# clock_generator.net
KiCad netlist of a schematic drawn in Altium Designer
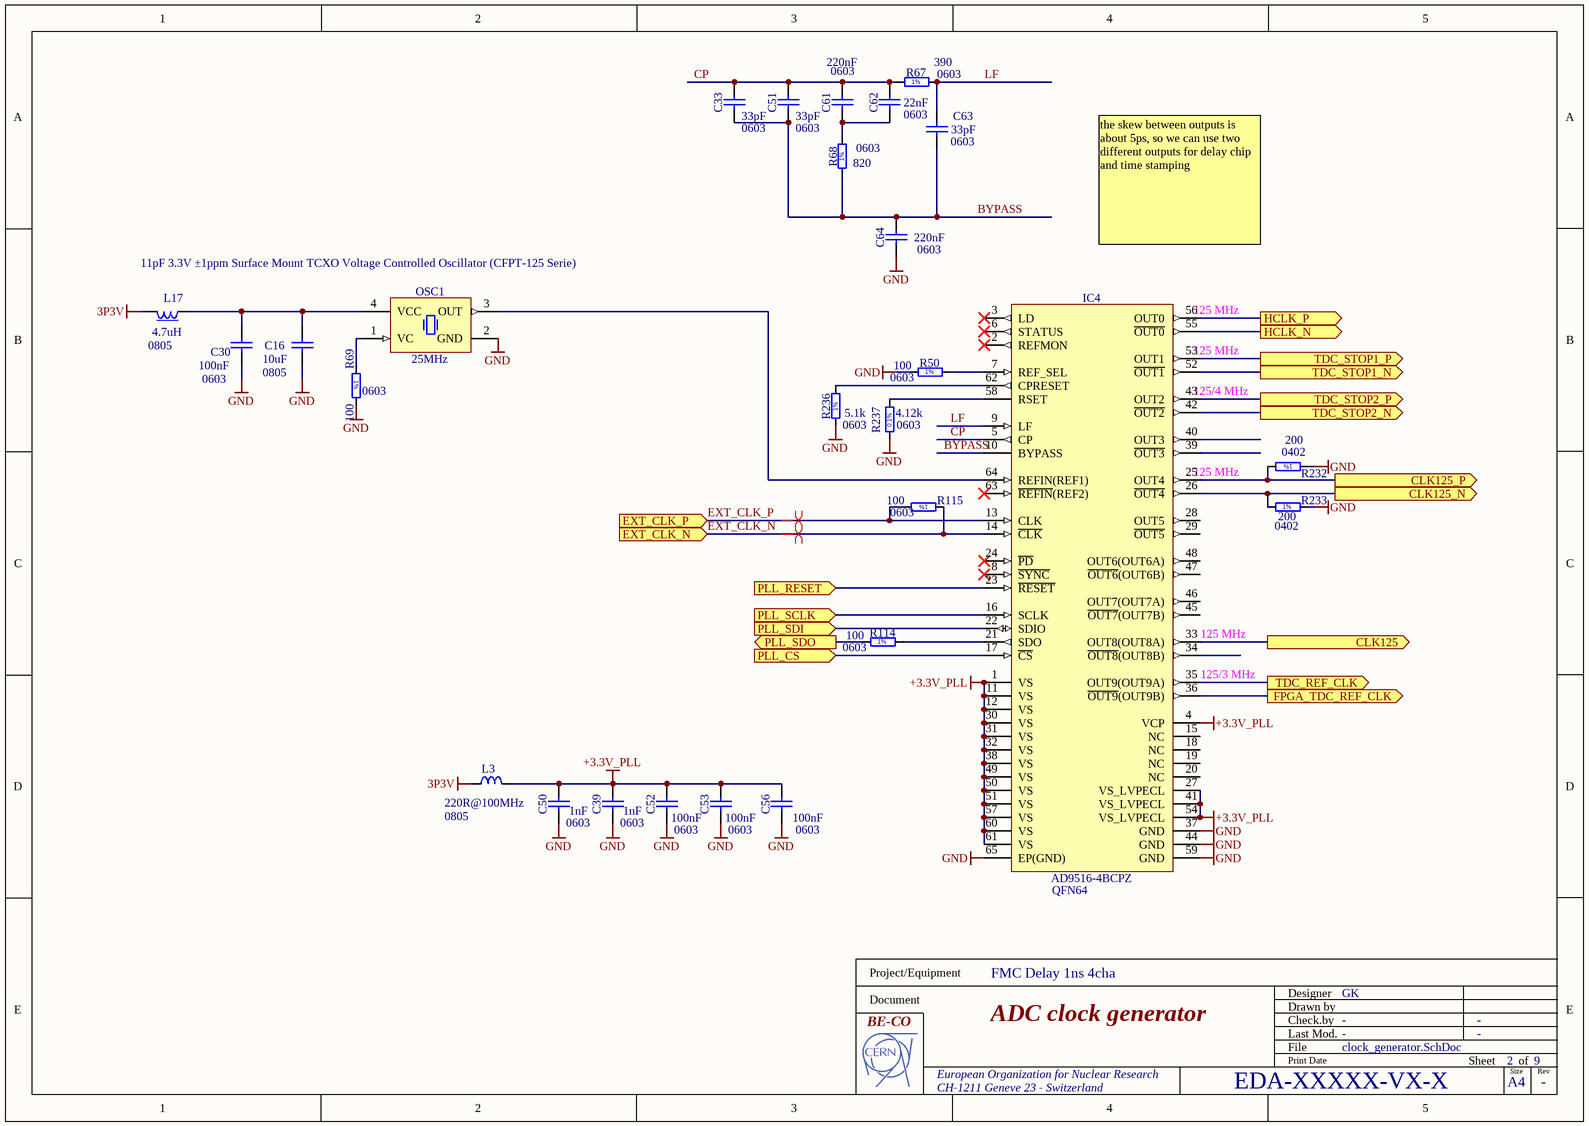
[diagram p0: clock_generator.SchDoc]

(export (version "E")
  (design (tool "Eeschema 10.0.6"))
  (components
    (comp (ref "C16")
      (value "10uF")
      (footprint "CAPC2012X135N")
      (description "Non-polarised capacitor")
      (fields
        (field (name "PART NUMBER") "CC0805_10UF_16V_10%_X5R")
        (field (name "VOLTAGE") "16V")
        (field (name "CASE") "0805")
        (field (name "AUTHOR") "CERN DEM JLC")
      )
      (libsource (lib "Capacitors") (part "Capacitor - non polarized"))
    )
    (comp (ref "C30")
      (value "100nF")
      (footprint "CAPC1608X87N")
      (description "Non-polarised capacitor")
      (fields
        (field (name "CASE") "0603")
        (field (name "MANUFACTURER1 PART NUMBER") "223858615649")
        (field (name "MANUFACTURER") "GENERIC")
        (field (name "AUTHOR") "CERN DEM JLC")
      )
      (libsource (lib "Capacitors") (part "Capacitor - non polarized"))
    )
    (comp (ref "C33")
      (value "33pF")
      (footprint "CAPC1608X87N")
      (description "Non-polarised capacitor")
      (fields
        (field (name "PART NUMBER") "CC0603_33PF_50V_5%_NP0")
        (field (name "VOLTAGE") "50V")
        (field (name "CASE") "0603")
        (field (name "AUTHOR") "CERN DEM JLC")
      )
      (libsource (lib "Capacitors") (part "Capacitor - non polarized"))
    )
    (comp (ref "C39")
      (value "1nF")
      (footprint "CAPC1608X87N")
      (description "Non-polarised capacitor")
      (fields
        (field (name "PART NUMBER") "CC0603_1NF_50V_10%_X7R")
        (field (name "VOLTAGE") "50V")
        (field (name "CASE") "0603")
        (field (name "AUTHOR") "CERN DEM JLC")
      )
      (libsource (lib "Capacitors") (part "Capacitor - non polarized"))
    )
    (comp (ref "C50")
      (value "1nF")
      (footprint "CAPC1608X87N")
      (description "Non-polarised capacitor")
      (fields
        (field (name "PART NUMBER") "CC0603_1NF_50V_10%_X7R")
        (field (name "VOLTAGE") "50V")
        (field (name "CASE") "0603")
        (field (name "AUTHOR") "CERN DEM JLC")
      )
      (libsource (lib "Capacitors") (part "Capacitor - non polarized"))
    )
    (comp (ref "C51")
      (value "33pF")
      (footprint "CAPC1608X87N")
      (description "Non-polarised capacitor")
      (fields
        (field (name "PART NUMBER") "CC0603_33PF_50V_5%_NP0")
        (field (name "VOLTAGE") "50V")
        (field (name "CASE") "0603")
        (field (name "AUTHOR") "CERN DEM JLC")
      )
      (libsource (lib "Capacitors") (part "Capacitor - non polarized"))
    )
    (comp (ref "C52")
      (value "100nF")
      (footprint "CAPC1608X87N")
      (description "Non-polarised capacitor")
      (fields
        (field (name "PART NUMBER") "CC0603_100NF_50V_10%_X7R")
        (field (name "VOLTAGE") "50V")
        (field (name "CASE") "0603")
        (field (name "AUTHOR") "CERN DEM JLC")
      )
      (libsource (lib "Capacitors") (part "Capacitor - non polarized"))
    )
    (comp (ref "C53")
      (value "100nF")
      (footprint "CAPC1608X87N")
      (description "Non-polarised capacitor")
      (fields
        (field (name "PART NUMBER") "CC0603_100NF_50V_10%_X7R")
        (field (name "VOLTAGE") "50V")
        (field (name "CASE") "0603")
        (field (name "AUTHOR") "CERN DEM JLC")
      )
      (libsource (lib "Capacitors") (part "Capacitor - non polarized"))
    )
    (comp (ref "C56")
      (value "100nF")
      (footprint "CAPC1608X87N")
      (description "Non-polarised capacitor")
      (fields
        (field (name "PART NUMBER") "CC0603_100NF_50V_10%_X7R")
        (field (name "VOLTAGE") "50V")
        (field (name "CASE") "0603")
        (field (name "AUTHOR") "CERN DEM JLC")
      )
      (libsource (lib "Capacitors") (part "Capacitor - non polarized"))
    )
    (comp (ref "C61")
      (value "220nF")
      (footprint "CAPC1608X87N")
      (description "Non-polarised capacitor")
      (fields
        (field (name "PART NUMBER") "CC0603_220NF_16V_+80%-20%_Y5V")
        (field (name "VOLTAGE") "16V")
        (field (name "CASE") "0603")
        (field (name "AUTHOR") "CERN DEM JLC")
      )
      (libsource (lib "Capacitors") (part "Capacitor - non polarized"))
    )
    (comp (ref "C62")
      (value "22nF")
      (footprint "CAPC1608X87N")
      (description "Non-polarised capacitor")
      (fields
        (field (name "PART NUMBER") "CC0603_22NF_50V_10%_X7R")
        (field (name "VOLTAGE") "50V")
        (field (name "CASE") "0603")
        (field (name "AUTHOR") "CERN DEM JLC")
      )
      (libsource (lib "Capacitors") (part "Capacitor - non polarized"))
    )
    (comp (ref "C63")
      (value "33pF")
      (footprint "CAPC1608X87N")
      (description "Non-polarised capacitor")
      (fields
        (field (name "PART NUMBER") "CC0603_33PF_50V_5%_NP0")
        (field (name "VOLTAGE") "50V")
        (field (name "CASE") "0603")
        (field (name "AUTHOR") "CERN DEM JLC")
      )
      (libsource (lib "Capacitors") (part "Capacitor - non polarized"))
    )
    (comp (ref "C64")
      (value "220nF")
      (footprint "CAPC1608X87N")
      (description "Non-polarised capacitor")
      (fields
        (field (name "PART NUMBER") "CC0603_220NF_16V_+80%-20%_Y5V")
        (field (name "VOLTAGE") "16V")
        (field (name "CASE") "0603")
        (field (name "AUTHOR") "CERN DEM JLC")
      )
      (libsource (lib "Capacitors") (part "Capacitor - non polarized"))
    )
    (comp (ref "IC4")
      (value "AD9516-4BCPZ")
      (footprint "QFN50P900X900X100-65N-S635")
      (description "14-Output Clock Generator with Integrated 1.6 GHz VCO")
      (fields
        (field (name "MANUFACTURER") "ANALOG DEVICES")
        (field (name "CASE") "QFN64")
        (field (name "AUTHOR") "CERN DEM JLC")
      )
      (libsource (lib "ICs And Semiconductors") (part "AD9516-4"))
    )
    (comp (ref "L3")
      (value "220R@100MHz")
      (footprint "INDC2012X105N")
      (description "Inductor")
      (fields
        (field (name "PART NUMBER") "IND0805_MURATA_BLM21PG221SN1D")
        (field (name "POWER") "2A")
        (field (name "CASE") "0805")
        (field (name "AUTHOR") "CERN DEM JLC")
      )
      (libsource (lib "Inductors & Transformers") (part "Inductor"))
    )
    (comp (ref "L17")
      (value "4.7uH")
      (footprint "INDC2012X145N")
      (description "Inductor With Magnetic core")
      (fields
        (field (name "PART NUMBER") "IND0805_4.7UH_20%_KEMET_L-DWI")
        (field (name "POWER") "360mA")
        (field (name "CASE") "0805")
        (field (name "AUTHOR") "CERN DEM JLC")
      )
      (libsource (lib "Inductors & Transformers") (part "Inductor With Magnetic core"))
    )
    (comp (ref "OSC1")
      (value "25MHz")
      (footprint "OSC_RAKON_IVT3200C")
      (description "Oscillator 4 pins 1=Voltage Control 2=GND 3=OUT 4=VCC")
      (fields
        (field (name "PART NUMBER") "OSC_25MHZ_RAKON_IVT3205CR")
        (field (name "PART DESCRIPTION") "11pF 3.3V ±1ppm Surface Mount TCXO Voltage Controlled Oscillator (CFPT-125 Serie)")
        (field (name "MANUFACTURER") "RAKON")
        (field (name "AUTHOR") "CERN DEM JLC")
      )
      (libsource (lib "ICs And Semiconductors") (part "Oscillator 1VC 2GND 3OUT 4VCC"))
    )
    (comp (ref "R50")
      (value "100")
      (footprint "RESC1608X55N")
      (description "Resistor - 1%")
      (fields
        (field (name "PART NUMBER") "R0603_100R_1%_0.1W_100PPM")
        (field (name "POWER") "0.1W")
        (field (name "CASE") "0603")
        (field (name "AUTHOR") "CERN DEM JLC")
      )
      (libsource (lib "Resistors") (part "Resistor - 1%"))
    )
    (comp (ref "R67")
      (value "390")
      (footprint "RESC1608X55N")
      (description "Resistor - 1%")
      (fields
        (field (name "PART NUMBER") "R0603_390R_1%_0.1W_100PPM")
        (field (name "POWER") "0.1W")
        (field (name "CASE") "0603")
        (field (name "AUTHOR") "CERN DEM JLC")
      )
      (libsource (lib "Resistors") (part "Resistor - 1%"))
    )
    (comp (ref "R68")
      (value "820")
      (footprint "RESC1608X55N")
      (description "Resistor - 1%")
      (fields
        (field (name "PART NUMBER") "R0603_820R_1%_0.1W_100PPM")
        (field (name "POWER") "0.1W")
        (field (name "CASE") "0603")
        (field (name "AUTHOR") "CERN DEM JLC")
      )
      (libsource (lib "Resistors") (part "Resistor - 1%"))
    )
    (comp (ref "R69")
      (value "100")
      (footprint "RESC1608X55N")
      (description "Resistor - 1%")
      (fields
        (field (name "PART NUMBER") "R0603_100R_1%_0.1W_100PPM")
        (field (name "POWER") "0.1W")
        (field (name "CASE") "0603")
        (field (name "AUTHOR") "CERN DEM JLC")
      )
      (libsource (lib "Resistors") (part "Resistor - 1%"))
    )
    (comp (ref "R114")
      (value "100")
      (footprint "RESC1608X55N")
      (description "Resistor - 1%")
      (fields
        (field (name "PART NUMBER") "R0603_100R_1%_0.1W_100PPM")
        (field (name "POWER") "0.1W")
        (field (name "CASE") "0603")
        (field (name "AUTHOR") "CERN DEM JLC")
      )
      (libsource (lib "Resistors") (part "Resistor - 1%"))
    )
    (comp (ref "R115")
      (value "100")
      (footprint "RESC1608X55N")
      (description "Resistor - 1%")
      (fields
        (field (name "PART NUMBER") "R0603_100R_1%_0.1W_100PPM")
        (field (name "POWER") "0.1W")
        (field (name "CASE") "0603")
        (field (name "AUTHOR") "CERN DEM JLC")
      )
      (libsource (lib "Resistors") (part "Resistor - 1%"))
    )
    (comp (ref "R232")
      (value "200")
      (footprint "RESC1005X40N")
      (description "Resistor - 1%")
      (fields
        (field (name "PART NUMBER") "R0402_200R_1%_0.0625W_100PPM")
        (field (name "POWER") "0.0625W")
        (field (name "CASE") "0402")
        (field (name "AUTHOR") "CERN DEM JLC")
      )
      (libsource (lib "Resistors") (part "Resistor - 1%"))
    )
    (comp (ref "R233")
      (value "200")
      (footprint "RESC1005X40N")
      (description "Resistor - 1%")
      (fields
        (field (name "PART NUMBER") "R0402_200R_1%_0.0625W_100PPM")
        (field (name "POWER") "0.0625W")
        (field (name "CASE") "0402")
        (field (name "AUTHOR") "CERN DEM JLC")
      )
      (libsource (lib "Resistors") (part "Resistor - 1%"))
    )
    (comp (ref "R236")
      (value "5.1k")
      (footprint "RESC1608X55N")
      (description "Resistor - 1%")
      (fields
        (field (name "PART NUMBER") "R0603_5K1_1%_0.1W_100PPM")
        (field (name "POWER") "0.1W")
        (field (name "CASE") "0603")
        (field (name "AUTHOR") "CERN DEM JLC")
      )
      (libsource (lib "Resistors") (part "Resistor - 1%"))
    )
    (comp (ref "R237")
      (value "4.12k")
      (footprint "RESC1608X55N")
      (description "Resistor - 0.1%")
      (fields
        (field (name "PART NUMBER") "R0603_4K12_0.1%_0.063W_10PPM")
        (field (name "POWER") "0.063W")
        (field (name "CASE") "0603")
        (field (name "AUTHOR") "CERN DEM JLC")
      )
      (libsource (lib "Resistors") (part "Resistor - 0.1%"))
    )
  )
  (nets
    (net (code "1") (name "+3.3V_PLL") (class "Default")
      (node (ref "C39") (pin "2") (pinfunction "2_2") (pintype "passive"))
      (node (ref "C50") (pin "2") (pinfunction "2_2") (pintype "passive"))
      (node (ref "C52") (pin "2") (pinfunction "2_2") (pintype "passive"))
      (node (ref "C53") (pin "2") (pinfunction "2_2") (pintype "passive"))
      (node (ref "C56") (pin "2") (pinfunction "2_2") (pintype "passive"))
      (node (ref "IC4") (pin "1") (pinfunction "VS_1") (pintype "power_in"))
      (node (ref "IC4") (pin "11") (pinfunction "VS_11") (pintype "power_in"))
      (node (ref "IC4") (pin "12") (pinfunction "VS_12") (pintype "power_in"))
      (node (ref "IC4") (pin "27") (pinfunction "VS_LVPECL_27") (pintype "power_in"))
      (node (ref "IC4") (pin "30") (pinfunction "VS_30") (pintype "power_in"))
      (node (ref "IC4") (pin "31") (pinfunction "VS_31") (pintype "power_in"))
      (node (ref "IC4") (pin "32") (pinfunction "VS_32") (pintype "power_in"))
      (node (ref "IC4") (pin "38") (pinfunction "VS_38") (pintype "power_in"))
      (node (ref "IC4") (pin "4") (pinfunction "VCP_4") (pintype "power_in"))
      (node (ref "IC4") (pin "41") (pinfunction "VS_LVPECL_41") (pintype "power_in"))
      (node (ref "IC4") (pin "49") (pinfunction "VS_49") (pintype "power_in"))
      (node (ref "IC4") (pin "50") (pinfunction "VS_50") (pintype "power_in"))
      (node (ref "IC4") (pin "51") (pinfunction "VS_51") (pintype "power_in"))
      (node (ref "IC4") (pin "54") (pinfunction "VS_LVPECL_54") (pintype "power_in"))
      (node (ref "IC4") (pin "57") (pinfunction "VS_57") (pintype "power_in"))
      (node (ref "IC4") (pin "60") (pinfunction "VS_60") (pintype "power_in"))
      (node (ref "IC4") (pin "61") (pinfunction "VS_61") (pintype "power_in"))
      (node (ref "L3") (pin "2") (pinfunction "2_2") (pintype "passive"))
    )
    (net (code "2") (name "/BYPASS") (class "Default")
      (node (ref "C33") (pin "1") (pinfunction "1_1") (pintype "passive"))
      (node (ref "C51") (pin "1") (pinfunction "1_1") (pintype "passive"))
      (node (ref "C63") (pin "1") (pinfunction "1_1") (pintype "passive"))
      (node (ref "C64") (pin "2") (pinfunction "2_2") (pintype "passive"))
      (node (ref "IC4") (pin "10") (pinfunction "BYPASS_10") (pintype "passive"))
      (node (ref "R68") (pin "1") (pinfunction "1_1") (pintype "passive"))
    )
    (net (code "3") (name "/CLK125") (class "Default")
      (node (ref "IC4") (pin "33") (pinfunction "OUT8(OUT8A)_33") (pintype "output"))
    )
    (net (code "4") (name "/CLK125_N") (class "Default")
      (node (ref "IC4") (pin "26") (pinfunction "OUT4_26") (pintype "output"))
      (node (ref "R233") (pin "1") (pinfunction "1_1") (pintype "passive"))
    )
    (net (code "5") (name "/CLK125_P") (class "Default")
      (node (ref "IC4") (pin "25") (pinfunction "OUT4_25") (pintype "output"))
      (node (ref "R232") (pin "2") (pinfunction "2_2") (pintype "passive"))
    )
    (net (code "6") (name "/CP") (class "Default")
      (node (ref "C33") (pin "2") (pinfunction "2_2") (pintype "passive"))
      (node (ref "C51") (pin "2") (pinfunction "2_2") (pintype "passive"))
      (node (ref "C61") (pin "2") (pinfunction "2_2") (pintype "passive"))
      (node (ref "C62") (pin "2") (pinfunction "2_2") (pintype "passive"))
      (node (ref "IC4") (pin "5") (pinfunction "CP_5") (pintype "output"))
      (node (ref "R67") (pin "1") (pinfunction "1_1") (pintype "passive"))
    )
    (net (code "7") (name "/EXT_CLK_N") (class "Default")
      (node (ref "IC4") (pin "14") (pinfunction "CLK_14") (pintype "input"))
      (node (ref "R115") (pin "1") (pinfunction "1_1") (pintype "passive"))
    )
    (net (code "8") (name "/EXT_CLK_P") (class "Default")
      (node (ref "IC4") (pin "13") (pinfunction "CLK_13") (pintype "input"))
      (node (ref "R115") (pin "2") (pinfunction "2_2") (pintype "passive"))
    )
    (net (code "9") (name "/FPGA_TDC_REF_CLK") (class "Default")
      (node (ref "IC4") (pin "36") (pinfunction "~{OUT9}(OUT9B)_36") (pintype "output"))
    )
    (net (code "10") (name "/HCLK_N") (class "Default")
      (node (ref "IC4") (pin "55") (pinfunction "OUT0_55") (pintype "output"))
    )
    (net (code "11") (name "/HCLK_P") (class "Default")
      (node (ref "IC4") (pin "56") (pinfunction "OUT0_56") (pintype "output"))
    )
    (net (code "12") (name "/LF") (class "Default")
      (node (ref "C63") (pin "2") (pinfunction "2_2") (pintype "passive"))
      (node (ref "IC4") (pin "9") (pinfunction "LF_9") (pintype "input"))
      (node (ref "R67") (pin "2") (pinfunction "2_2") (pintype "passive"))
    )
    (net (code "13") (name "/PLL_CS") (class "Default")
      (node (ref "IC4") (pin "17") (pinfunction "CS_17") (pintype "input"))
    )
    (net (code "14") (name "/PLL_RESET") (class "Default")
      (node (ref "IC4") (pin "23") (pinfunction "RESET_23") (pintype "input"))
    )
    (net (code "15") (name "/PLL_SCLK") (class "Default")
      (node (ref "IC4") (pin "16") (pinfunction "SCLK_16") (pintype "input"))
    )
    (net (code "16") (name "/PLL_SDI") (class "Default")
      (node (ref "IC4") (pin "22") (pinfunction "SDIO_22") (pintype "bidirectional"))
    )
    (net (code "17") (name "/PLL_SDO") (class "Default")
      (node (ref "R114") (pin "1") (pinfunction "1_1") (pintype "passive"))
    )
    (net (code "18") (name "/TDC_REF_CLK") (class "Default")
      (node (ref "IC4") (pin "35") (pinfunction "OUT9(OUT9A)_35") (pintype "output"))
    )
    (net (code "19") (name "/TDC_STOP1_N") (class "Default")
      (node (ref "IC4") (pin "52") (pinfunction "OUT1_52") (pintype "output"))
    )
    (net (code "20") (name "/TDC_STOP1_P") (class "Default")
      (node (ref "IC4") (pin "53") (pinfunction "OUT1_53") (pintype "output"))
    )
    (net (code "21") (name "/TDC_STOP2_N") (class "Default")
      (node (ref "IC4") (pin "42") (pinfunction "OUT2_42") (pintype "output"))
    )
    (net (code "22") (name "/TDC_STOP2_P") (class "Default")
      (node (ref "IC4") (pin "43") (pinfunction "OUT2_43") (pintype "output"))
    )
    (net (code "23") (name "3P3V") (class "Default")
      (node (ref "L17") (pin "2") (pinfunction "2_2") (pintype "passive"))
      (node (ref "L3") (pin "1") (pinfunction "1_1") (pintype "passive"))
    )
    (net (code "24") (name "GND") (class "Default")
      (node (ref "C16") (pin "1") (pinfunction "1_1") (pintype "passive"))
      (node (ref "C30") (pin "1") (pinfunction "1_1") (pintype "passive"))
      (node (ref "C39") (pin "1") (pinfunction "1_1") (pintype "passive"))
      (node (ref "C50") (pin "1") (pinfunction "1_1") (pintype "passive"))
      (node (ref "C52") (pin "1") (pinfunction "1_1") (pintype "passive"))
      (node (ref "C53") (pin "1") (pinfunction "1_1") (pintype "passive"))
      (node (ref "C56") (pin "1") (pinfunction "1_1") (pintype "passive"))
      (node (ref "C64") (pin "1") (pinfunction "1_1") (pintype "passive"))
      (node (ref "IC4") (pin "37") (pinfunction "GND_37") (pintype "power_in"))
      (node (ref "IC4") (pin "44") (pinfunction "GND_44") (pintype "power_in"))
      (node (ref "IC4") (pin "59") (pinfunction "GND_59") (pintype "power_in"))
      (node (ref "IC4") (pin "65") (pinfunction "EP(GND)_65") (pintype "power_in"))
      (node (ref "OSC1") (pin "2") (pinfunction "GND_2") (pintype "power_in"))
      (node (ref "R232") (pin "1") (pinfunction "1_1") (pintype "passive"))
      (node (ref "R233") (pin "2") (pinfunction "2_2") (pintype "passive"))
      (node (ref "R236") (pin "1") (pinfunction "1_1") (pintype "passive"))
      (node (ref "R237") (pin "1") (pinfunction "1_1") (pintype "passive"))
      (node (ref "R50") (pin "1") (pinfunction "1_1") (pintype "passive"))
      (node (ref "R69") (pin "2") (pinfunction "2_2") (pintype "passive"))
    )
    (net (code "25") (name "Net-(C61-Pad1)") (class "Default")
      (node (ref "C61") (pin "1") (pinfunction "1_1") (pintype "passive"))
      (node (ref "C62") (pin "1") (pinfunction "1_1") (pintype "passive"))
      (node (ref "R68") (pin "2") (pinfunction "2_2") (pintype "passive"))
    )
    (net (code "26") (name "Net-(IC4-CPRESET)") (class "Default")
      (node (ref "IC4") (pin "62") (pinfunction "CPRESET_62") (pintype "output"))
      (node (ref "R236") (pin "2") (pinfunction "2_2") (pintype "passive"))
    )
    (net (code "27") (name "Net-(IC4-REFIN(REF1))") (class "Default")
      (node (ref "IC4") (pin "64") (pinfunction "REFIN(REF1)_64") (pintype "input"))
      (node (ref "OSC1") (pin "3") (pinfunction "OUT_3") (pintype "output"))
    )
    (net (code "28") (name "Net-(IC4-REF_SEL)") (class "Default")
      (node (ref "IC4") (pin "7") (pinfunction "REF_SEL_7") (pintype "input"))
      (node (ref "R50") (pin "2") (pinfunction "2_2") (pintype "passive"))
    )
    (net (code "29") (name "Net-(IC4-RSET)") (class "Default")
      (node (ref "IC4") (pin "58") (pinfunction "RSET_58") (pintype "passive"))
      (node (ref "R237") (pin "2") (pinfunction "2_2") (pintype "passive"))
    )
    (net (code "30") (name "Net-(IC4-SDO)") (class "Default")
      (node (ref "IC4") (pin "21") (pinfunction "SDO_21") (pintype "output"))
      (node (ref "R114") (pin "2") (pinfunction "2_2") (pintype "passive"))
    )
    (net (code "31") (name "Net-(OSC1-VC)") (class "Default")
      (node (ref "OSC1") (pin "1") (pinfunction "VC_1") (pintype "input"))
      (node (ref "R69") (pin "1") (pinfunction "1_1") (pintype "passive"))
    )
    (net (code "32") (name "Net-(OSC1-VCC)") (class "Default")
      (node (ref "C16") (pin "2") (pinfunction "2_2") (pintype "passive"))
      (node (ref "C30") (pin "2") (pinfunction "2_2") (pintype "passive"))
      (node (ref "L17") (pin "1") (pinfunction "1_1") (pintype "passive"))
      (node (ref "OSC1") (pin "4") (pinfunction "VCC_4") (pintype "power_in"))
    )
    (net (code "33") (name "unconnected-(IC4-LD-Pad3)") (class "Default")
      (node (ref "IC4") (pin "3") (pinfunction "LD_3") (pintype "output+no_connect"))
    )
    (net (code "34") (name "unconnected-(IC4-NC-Pad15)") (class "Default")
      (node (ref "IC4") (pin "15") (pinfunction "NC_15") (pintype "passive"))
    )
    (net (code "35") (name "unconnected-(IC4-NC-Pad18)") (class "Default")
      (node (ref "IC4") (pin "18") (pinfunction "NC_18") (pintype "passive"))
    )
    (net (code "36") (name "unconnected-(IC4-NC-Pad19)") (class "Default")
      (node (ref "IC4") (pin "19") (pinfunction "NC_19") (pintype "passive"))
    )
    (net (code "37") (name "unconnected-(IC4-NC-Pad20)") (class "Default")
      (node (ref "IC4") (pin "20") (pinfunction "NC_20") (pintype "passive"))
    )
    (net (code "38") (name "unconnected-(IC4-OUT3-Pad39)") (class "Default")
      (node (ref "IC4") (pin "39") (pinfunction "OUT3_39") (pintype "output"))
    )
    (net (code "39") (name "unconnected-(IC4-OUT3-Pad40)") (class "Default")
      (node (ref "IC4") (pin "40") (pinfunction "OUT3_40") (pintype "output"))
    )
    (net (code "40") (name "unconnected-(IC4-OUT5-Pad28)") (class "Default")
      (node (ref "IC4") (pin "28") (pinfunction "OUT5_28") (pintype "output"))
    )
    (net (code "41") (name "unconnected-(IC4-OUT5-Pad29)") (class "Default")
      (node (ref "IC4") (pin "29") (pinfunction "OUT5_29") (pintype "output"))
    )
    (net (code "42") (name "unconnected-(IC4-OUT6(OUT6A)-Pad48)") (class "Default")
      (node (ref "IC4") (pin "48") (pinfunction "OUT6(OUT6A)_48") (pintype "output"))
    )
    (net (code "43") (name "unconnected-(IC4-OUT7(OUT7A)-Pad46)") (class "Default")
      (node (ref "IC4") (pin "46") (pinfunction "OUT7(OUT7A)_46") (pintype "output"))
    )
    (net (code "44") (name "unconnected-(IC4-PD-Pad24)") (class "Default")
      (node (ref "IC4") (pin "24") (pinfunction "PD_24") (pintype "input+no_connect"))
    )
    (net (code "45") (name "unconnected-(IC4-REFMON-Pad2)") (class "Default")
      (node (ref "IC4") (pin "2") (pinfunction "REFMON_2") (pintype "output+no_connect"))
    )
    (net (code "46") (name "unconnected-(IC4-STATUS-Pad6)") (class "Default")
      (node (ref "IC4") (pin "6") (pinfunction "STATUS_6") (pintype "output+no_connect"))
    )
    (net (code "47") (name "unconnected-(IC4-SYNC-Pad8)") (class "Default")
      (node (ref "IC4") (pin "8") (pinfunction "SYNC_8") (pintype "input+no_connect"))
    )
    (net (code "48") (name "unconnected-(IC4-~{OUT6}(OUT6B)-Pad47)") (class "Default")
      (node (ref "IC4") (pin "47") (pinfunction "~{OUT6}(OUT6B)_47") (pintype "output"))
    )
    (net (code "49") (name "unconnected-(IC4-~{OUT7}(OUT7B)-Pad45)") (class "Default")
      (node (ref "IC4") (pin "45") (pinfunction "~{OUT7}(OUT7B)_45") (pintype "output"))
    )
    (net (code "50") (name "unconnected-(IC4-~{OUT8}(OUT8B)-Pad34)") (class "Default")
      (node (ref "IC4") (pin "34") (pinfunction "~{OUT8}(OUT8B)_34") (pintype "output"))
    )
    (net (code "51") (name "unconnected-(IC4-~{REFIN}(REF2)-Pad63)") (class "Default")
      (node (ref "IC4") (pin "63") (pinfunction "~{REFIN}(REF2)_63") (pintype "input+no_connect"))
    )
  )
)
